# Sheet1.net
KiCad netlist of a schematic drawn in Altium Designer
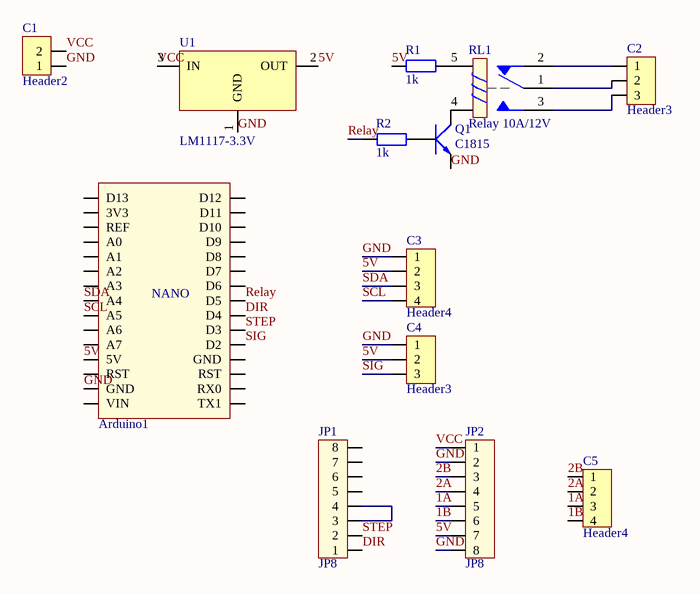
[diagram p0: Sheet1.SchDoc]

(export (version "E")
  (design (tool "Eeschema 10.0.6"))
  (components
    (comp (ref "Arduino1")
      (value "Arduino Nano")
      (footprint "Arduino Nano")
      (description "Arduino NANO")
      (libsource (lib "LIBRARY") (part "Arduino Nano"))
    )
    (comp (ref "C1")
      (value "Header2")
      (footprint "HDR2")
      (description "Header IDC, 2 x 1 Pin Vertical 2.54mm Pitch (Non-Boxed, Male)")
      (fields
        (field (name "MANUFACTURER") "Würth Elektronik eiSos GmbH")
        (field (name "PARTNO") "613002143121")
        (field (name "CREATED BY") "Karrer Zheng")
      )
      (libsource (lib "LIBRARY") (part "Header2"))
    )
    (comp (ref "C2")
      (value "Header3")
      (footprint "Header3")
      (description "Header IDC, 3 x 1 Pin Vertical 2.54mm Pitch (Non-Boxed, Male)")
      (fields
        (field (name "MANUFACTURER") "Würth Elektronik eiSos GmbH")
        (field (name "PARTNO") "613002143121")
        (field (name "CREATED BY") "Karrer Zheng")
      )
      (libsource (lib "LIBRARY") (part "Header3"))
    )
    (comp (ref "C3")
      (value "Header4")
      (footprint "HDR4")
      (description "Header IDC, 4 x 1 Pin Vertical 2.54mm Pitch (Non-Boxed, Male)")
      (fields
        (field (name "MANUFACTURER") "Würth Elektronik eiSos GmbH")
        (field (name "PARTNO") "613002143121")
        (field (name "CREATED BY") "Karrer Zheng")
      )
      (libsource (lib "LIBRARY") (part "Header4"))
    )
    (comp (ref "C4")
      (value "Header3")
      (footprint "Header3")
      (description "Header IDC, 3 x 1 Pin Vertical 2.54mm Pitch (Non-Boxed, Male)")
      (fields
        (field (name "MANUFACTURER") "Würth Elektronik eiSos GmbH")
        (field (name "PARTNO") "613002143121")
        (field (name "CREATED BY") "Karrer Zheng")
      )
      (libsource (lib "LIBRARY") (part "Header3"))
    )
    (comp (ref "C5")
      (value "Header4")
      (footprint "HDR4")
      (description "Header IDC, 4 x 1 Pin Vertical 2.54mm Pitch (Non-Boxed, Male)")
      (fields
        (field (name "MANUFACTURER") "Würth Elektronik eiSos GmbH")
        (field (name "PARTNO") "613002143121")
        (field (name "CREATED BY") "Karrer Zheng")
      )
      (libsource (lib "LIBRARY") (part "Header4"))
    )
    (comp (ref "JP1")
      (value "JP8")
      (footprint "Header8")
      (description "Connector 8")
      (libsource (lib "") (part "Header8_1"))
    )
    (comp (ref "JP2")
      (value "JP8")
      (footprint "Header8")
      (description "Connector 8")
      (libsource (lib "LIBRARY") (part "Header8"))
    )
    (comp (ref "Q1")
      (value "C1815")
      (footprint "QTO-92")
      (description "NPN 600mW, ECB")
      (libsource (lib "syhaunguyen") (part "C1815"))
    )
    (comp (ref "R1")
      (value "1k")
      (footprint "R1/2W")
      (description "Resistor 1/4W")
      (libsource (lib "syhaunguyen") (part "R1/4W"))
    )
    (comp (ref "R2")
      (value "1k")
      (footprint "R1/2W")
      (description "Resistor 1/4W")
      (libsource (lib "syhaunguyen") (part "R1/4W"))
    )
    (comp (ref "RL1")
      (value "Relay 10A/12V")
      (footprint "RL_SPDT_10A")
      (description "Relay SPDT,10A - 12VDC 5 Pin")
      (libsource (lib "syhaunguyen") (part "Relay 1"))
    )
    (comp (ref "U1")
      (value "LM1117-3.3V")
      (footprint "SOT223")
      (description "800mA Low-Dropout Linear Regulator")
      (fields (field (name "CREATOR") "Nguyen Ba Bien"))
      (libsource (lib "LIBRARY") (part "LM1117"))
    )
  )
  (nets
    (net (code "1") (name "/1A") (class "Default")
      (node (ref "C5") (pin "3") (pinfunction "3_3") (pintype "passive"))
      (node (ref "JP2") (pin "5") (pinfunction "5_5") (pintype "passive"))
    )
    (net (code "2") (name "/1B") (class "Default")
      (node (ref "C5") (pin "4") (pinfunction "4_4") (pintype "passive"))
      (node (ref "JP2") (pin "6") (pinfunction "6_6") (pintype "passive"))
    )
    (net (code "3") (name "/2A") (class "Default")
      (node (ref "C5") (pin "2") (pinfunction "2_2") (pintype "passive"))
      (node (ref "JP2") (pin "4") (pinfunction "4_4") (pintype "passive"))
    )
    (net (code "4") (name "/2B") (class "Default")
      (node (ref "C5") (pin "1") (pinfunction "1_1") (pintype "passive"))
      (node (ref "JP2") (pin "3") (pinfunction "3_3") (pintype "passive"))
    )
    (net (code "5") (name "/5V") (class "Default")
      (node (ref "Arduino1") (pin "5V") (pinfunction "5V_5V") (pintype "passive"))
      (node (ref "C3") (pin "2") (pinfunction "2_2") (pintype "passive"))
      (node (ref "C4") (pin "2") (pinfunction "2_2") (pintype "passive"))
      (node (ref "JP2") (pin "7") (pinfunction "7_7") (pintype "passive"))
      (node (ref "R1") (pin "1") (pinfunction "1_1") (pintype "passive"))
      (node (ref "U1") (pin "2") (pinfunction "OUT_2") (pintype "passive"))
    )
    (net (code "6") (name "/DIR") (class "Default")
      (node (ref "Arduino1") (pin "D4") (pinfunction "D4_D4") (pintype "passive"))
      (node (ref "JP1") (pin "1") (pinfunction "1_1") (pintype "passive"))
    )
    (net (code "7") (name "/GND") (class "Default")
      (node (ref "Arduino1") (pin "GND") (pinfunction "GND_GND") (pintype "passive"))
      (node (ref "C1") (pin "1") (pinfunction "1_1") (pintype "passive"))
      (node (ref "C3") (pin "1") (pinfunction "1_1") (pintype "passive"))
      (node (ref "C4") (pin "1") (pinfunction "1_1") (pintype "passive"))
      (node (ref "JP2") (pin "2") (pinfunction "2_2") (pintype "passive"))
      (node (ref "JP2") (pin "8") (pinfunction "8_8") (pintype "passive"))
      (node (ref "Q1") (pin "1") (pinfunction "E_1") (pintype "passive"))
      (node (ref "U1") (pin "1") (pinfunction "GND_1") (pintype "passive"))
    )
    (net (code "8") (name "/Relay") (class "Default")
      (node (ref "Arduino1") (pin "D5") (pinfunction "D5_D5") (pintype "passive"))
      (node (ref "R2") (pin "1") (pinfunction "1_1") (pintype "passive"))
    )
    (net (code "9") (name "/SCL") (class "Default")
      (node (ref "Arduino1") (pin "A5") (pinfunction "A5_A5") (pintype "passive"))
      (node (ref "C3") (pin "4") (pinfunction "4_4") (pintype "passive"))
    )
    (net (code "10") (name "/SDA") (class "Default")
      (node (ref "Arduino1") (pin "A4") (pinfunction "A4_A4") (pintype "passive"))
      (node (ref "C3") (pin "3") (pinfunction "3_3") (pintype "passive"))
    )
    (net (code "11") (name "/SIG") (class "Default")
      (node (ref "Arduino1") (pin "D2") (pinfunction "D2_D2") (pintype "passive"))
      (node (ref "C4") (pin "3") (pinfunction "3_3") (pintype "passive"))
    )
    (net (code "12") (name "/STEP") (class "Default")
      (node (ref "Arduino1") (pin "D3") (pinfunction "D3_D3") (pintype "passive"))
      (node (ref "JP1") (pin "2") (pinfunction "2_2") (pintype "passive"))
    )
    (net (code "13") (name "/VCC") (class "Default")
      (node (ref "C1") (pin "2") (pinfunction "2_2") (pintype "passive"))
      (node (ref "JP2") (pin "1") (pinfunction "1_1") (pintype "passive"))
      (node (ref "U1") (pin "3") (pinfunction "IN_3") (pintype "passive"))
    )
    (net (code "14") (name "Net-(C2-Pad1)") (class "Default")
      (node (ref "C2") (pin "1") (pinfunction "1_1") (pintype "passive"))
      (node (ref "RL1") (pin "2") (pinfunction "2_2") (pintype "passive"))
    )
    (net (code "15") (name "Net-(C2-Pad2)") (class "Default")
      (node (ref "C2") (pin "2") (pinfunction "2_2") (pintype "passive"))
      (node (ref "RL1") (pin "1") (pinfunction "1_1") (pintype "passive"))
    )
    (net (code "16") (name "Net-(C2-Pad3)") (class "Default")
      (node (ref "C2") (pin "3") (pinfunction "3_3") (pintype "passive"))
      (node (ref "RL1") (pin "3") (pinfunction "3_3") (pintype "passive"))
    )
    (net (code "17") (name "Net-(JP1-Pad3)") (class "Default")
      (node (ref "JP1") (pin "3") (pinfunction "3_3") (pintype "passive"))
      (node (ref "JP1") (pin "4") (pinfunction "4_4") (pintype "passive"))
    )
    (net (code "18") (name "Net-(Q1-B)") (class "Default")
      (node (ref "Q1") (pin "3") (pinfunction "B_3") (pintype "passive"))
      (node (ref "R2") (pin "2") (pinfunction "2_2") (pintype "passive"))
    )
    (net (code "19") (name "Net-(Q1-C)") (class "Default")
      (node (ref "Q1") (pin "2") (pinfunction "C_2") (pintype "passive"))
      (node (ref "RL1") (pin "4") (pinfunction "4_4") (pintype "passive"))
    )
    (net (code "20") (name "Net-(R1-Pad2)") (class "Default")
      (node (ref "R1") (pin "2") (pinfunction "2_2") (pintype "passive"))
      (node (ref "RL1") (pin "5") (pinfunction "5_5") (pintype "passive"))
    )
    (net (code "21") (name "unconnected-(Arduino1-Pad3V3)") (class "Default")
      (node (ref "Arduino1") (pin "3V3") (pinfunction "3V3_3V3") (pintype "passive"))
    )
    (net (code "22") (name "unconnected-(Arduino1-PadA0)") (class "Default")
      (node (ref "Arduino1") (pin "A0") (pinfunction "A0_A0") (pintype "passive"))
    )
    (net (code "23") (name "unconnected-(Arduino1-PadA1)") (class "Default")
      (node (ref "Arduino1") (pin "A1") (pinfunction "A1_A1") (pintype "passive"))
    )
    (net (code "24") (name "unconnected-(Arduino1-PadA2)") (class "Default")
      (node (ref "Arduino1") (pin "A2") (pinfunction "A2_A2") (pintype "passive"))
    )
    (net (code "25") (name "unconnected-(Arduino1-PadA3)") (class "Default")
      (node (ref "Arduino1") (pin "A3") (pinfunction "A3_A3") (pintype "passive"))
    )
    (net (code "26") (name "unconnected-(Arduino1-PadA6)") (class "Default")
      (node (ref "Arduino1") (pin "A6") (pinfunction "A6_A6") (pintype "passive"))
    )
    (net (code "27") (name "unconnected-(Arduino1-PadA7)") (class "Default")
      (node (ref "Arduino1") (pin "A7") (pinfunction "A7_A7") (pintype "passive"))
    )
    (net (code "28") (name "unconnected-(Arduino1-PadD6)") (class "Default")
      (node (ref "Arduino1") (pin "D6") (pinfunction "D6_D6") (pintype "passive"))
    )
    (net (code "29") (name "unconnected-(Arduino1-PadD7)") (class "Default")
      (node (ref "Arduino1") (pin "D7") (pinfunction "D7_D7") (pintype "passive"))
    )
    (net (code "30") (name "unconnected-(Arduino1-PadD8)") (class "Default")
      (node (ref "Arduino1") (pin "D8") (pinfunction "D8_D8") (pintype "passive"))
    )
    (net (code "31") (name "unconnected-(Arduino1-PadD9)") (class "Default")
      (node (ref "Arduino1") (pin "D9") (pinfunction "D9_D9") (pintype "passive"))
    )
    (net (code "32") (name "unconnected-(Arduino1-PadD10)") (class "Default")
      (node (ref "Arduino1") (pin "D10") (pinfunction "D10_D10") (pintype "passive"))
    )
    (net (code "33") (name "unconnected-(Arduino1-PadD11)") (class "Default")
      (node (ref "Arduino1") (pin "D11") (pinfunction "D11_D11") (pintype "passive"))
    )
    (net (code "34") (name "unconnected-(Arduino1-PadD12)") (class "Default")
      (node (ref "Arduino1") (pin "D12") (pinfunction "D12_D12") (pintype "passive"))
    )
    (net (code "35") (name "unconnected-(Arduino1-PadD13)") (class "Default")
      (node (ref "Arduino1") (pin "D13") (pinfunction "D13_D13") (pintype "passive"))
    )
    (net (code "36") (name "unconnected-(Arduino1-PadGND)") (class "Default")
      (node (ref "Arduino1") (pin "GND") (pinfunction "GND_GND") (pintype "passive"))
    )
    (net (code "37") (name "unconnected-(Arduino1-PadREF)") (class "Default")
      (node (ref "Arduino1") (pin "REF") (pinfunction "REF_REF") (pintype "passive"))
    )
    (net (code "38") (name "unconnected-(Arduino1-PadRST)") (class "Default")
      (node (ref "Arduino1") (pin "RST") (pinfunction "RST_RST") (pintype "passive"))
    )
    (net (code "39") (name "unconnected-(Arduino1-PadRST)_1") (class "Default")
      (node (ref "Arduino1") (pin "RST") (pinfunction "RST_RST") (pintype "passive"))
    )
    (net (code "40") (name "unconnected-(Arduino1-PadRX0)") (class "Default")
      (node (ref "Arduino1") (pin "RX0") (pinfunction "RX0_RX0") (pintype "passive"))
    )
    (net (code "41") (name "unconnected-(Arduino1-PadTX1)") (class "Default")
      (node (ref "Arduino1") (pin "TX1") (pinfunction "TX1_TX1") (pintype "passive"))
    )
    (net (code "42") (name "unconnected-(Arduino1-PadVIN)") (class "Default")
      (node (ref "Arduino1") (pin "VIN") (pinfunction "VIN_VIN") (pintype "passive"))
    )
    (net (code "43") (name "unconnected-(JP1-Pad5)") (class "Default")
      (node (ref "JP1") (pin "5") (pinfunction "5_5") (pintype "passive"))
    )
    (net (code "44") (name "unconnected-(JP1-Pad6)") (class "Default")
      (node (ref "JP1") (pin "6") (pinfunction "6_6") (pintype "passive"))
    )
    (net (code "45") (name "unconnected-(JP1-Pad7)") (class "Default")
      (node (ref "JP1") (pin "7") (pinfunction "7_7") (pintype "passive"))
    )
    (net (code "46") (name "unconnected-(JP1-Pad8)") (class "Default")
      (node (ref "JP1") (pin "8") (pinfunction "8_8") (pintype "passive"))
    )
  )
)
